# sheet2.net
KiCad netlist of a schematic drawn in Altium Designer
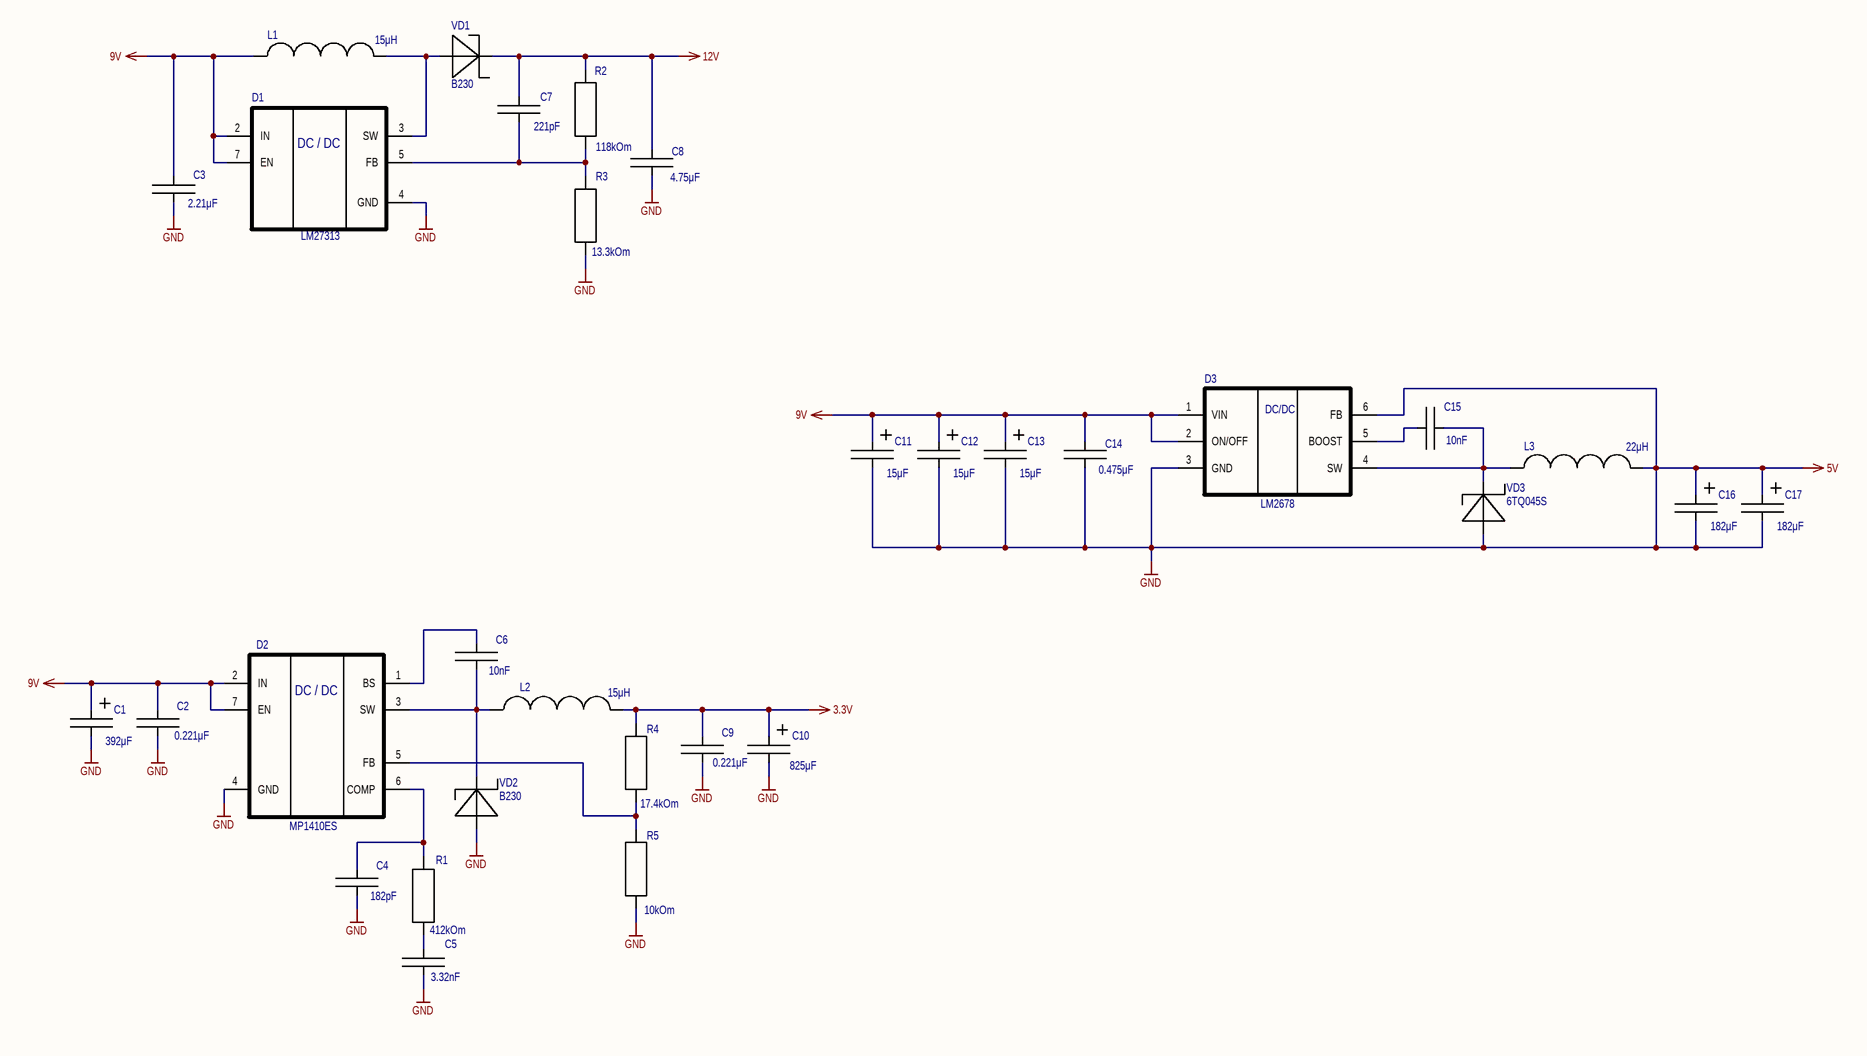
[diagram p0: sheet2.SchDoc]

(export (version "E")
  (design (tool "Eeschema 10.0.6"))
  (components
    (comp (ref "C1")
      (value "392μF")
      (fields (field (name "Comment") "392μFФ ±* * * *, *"))
      (libsource (lib "STO") (part "C+"))
    )
    (comp (ref "C2")
      (value "0.221μF")
      (fields (field (name "Comment") "0.221μFФ ±* * * *, *"))
      (libsource (lib "STO") (part "C"))
    )
    (comp (ref "C3")
      (value "2.21μF")
      (fields (field (name "Comment") "2.21μFФ ±* * * *, *"))
      (libsource (lib "STO") (part "C"))
    )
    (comp (ref "C4")
      (value "182pF")
      (fields (field (name "Comment") "182pFФ ±* * * *, *"))
      (libsource (lib "STO") (part "C"))
    )
    (comp (ref "C5")
      (value "3.32nF")
      (fields (field (name "Comment") "3.32nFФ ±* * * *, *"))
      (libsource (lib "STO") (part "C"))
    )
    (comp (ref "C6")
      (value "10nF")
      (fields (field (name "Comment") "10nFФ ±* * * *, *"))
      (libsource (lib "STO") (part "C"))
    )
    (comp (ref "C7")
      (value "221pF")
      (fields (field (name "Comment") "221pFФ ±* * * *, *"))
      (libsource (lib "STO") (part "C"))
    )
    (comp (ref "C8")
      (value "4.75μF")
      (fields (field (name "Comment") "4.75μFФ ±* * * *, *"))
      (libsource (lib "STO") (part "C"))
    )
    (comp (ref "C9")
      (value "0.221μF")
      (fields (field (name "Comment") "0.221μFФ ±* * * *, *"))
      (libsource (lib "STO") (part "C"))
    )
    (comp (ref "C10")
      (value "825μF")
      (fields (field (name "VOLTAGE") "6.3V") (field (name "Comment") "825μFФ ±* 6.3V * *, *"))
      (libsource (lib "STO") (part "C+"))
    )
    (comp (ref "C11")
      (value "15μF")
      (fields (field (name "Comment") "15μFФ ±* * * *, *"))
      (libsource (lib "STO") (part "C+"))
    )
    (comp (ref "C12")
      (value "15μF")
      (fields (field (name "Comment") "15μFФ ±* * * *, *"))
      (libsource (lib "STO") (part "C+"))
    )
    (comp (ref "C13")
      (value "15μF")
      (fields (field (name "Comment") "15μFФ ±* * * *, *"))
      (libsource (lib "STO") (part "C+"))
    )
    (comp (ref "C14")
      (value "0.475μF")
      (fields (field (name "Comment") "0.475μFФ ±* * * *, *"))
      (libsource (lib "STO") (part "C"))
    )
    (comp (ref "C15")
      (value "10nF")
      (fields (field (name "Comment") "10nFФ ±* * * *, *"))
      (libsource (lib "STO") (part "C"))
    )
    (comp (ref "C16")
      (value "182μF")
      (fields (field (name "Comment") "182μFФ ±* * * *, *"))
      (libsource (lib "STO") (part "C+"))
    )
    (comp (ref "C17")
      (value "182μF")
      (fields (field (name "Comment") "182μFФ ±* * * *, *"))
      (libsource (lib "STO") (part "C+"))
    )
    (comp (ref "D1") (value "LM27313") (libsource (lib "dop_elements") (part "LM27313")))
    (comp (ref "D2") (value "MP1410ES") (libsource (lib "dop_elements") (part "MP1410ES")))
    (comp (ref "D3") (value "LM2678") (libsource (lib "dop_elements") (part "LM2678")))
    (comp (ref "L1") (value "15μH") (libsource (lib "dop_elements") (part "L")))
    (comp (ref "L2") (value "15μH") (libsource (lib "dop_elements") (part "L")))
    (comp (ref "L3") (value "22μH") (libsource (lib "dop_elements") (part "L")))
    (comp (ref "R1")
      (value "412kOm")
      (fields (field (name "Comment") "412kOmОм ±* *, *"))
      (libsource (lib "STO") (part "R"))
    )
    (comp (ref "R2")
      (value "118kOm")
      (fields (field (name "Comment") "118kOmОм ±* *, *"))
      (libsource (lib "STO") (part "R"))
    )
    (comp (ref "R3")
      (value "13.3kOm")
      (fields (field (name "Comment") "13.3kOmОм ±* *, *"))
      (libsource (lib "STO") (part "R"))
    )
    (comp (ref "R4")
      (value "17.4kOm")
      (fields (field (name "Comment") "17.4kOmОм ±* *, *"))
      (libsource (lib "STO") (part "R"))
    )
    (comp (ref "R5")
      (value "10kOm")
      (fields (field (name "Comment") "10kOmОм ±* *, *"))
      (libsource (lib "STO") (part "R"))
    )
    (comp (ref "VD1") (value "B230") (libsource (lib "dop_elements") (part "diode_shottki")))
    (comp (ref "VD2") (value "B230") (libsource (lib "dop_elements") (part "diode_shottki")))
    (comp (ref "VD3") (value "6TQ045S") (libsource (lib "dop_elements") (part "diode_shottki")))
  )
  (nets
    (net (code "1") (name "3.3V") (class "Default")
      (node (ref "C10") (pin "1") (pinfunction "1_1") (pintype "passive"))
      (node (ref "C9") (pin "2") (pinfunction "2_2") (pintype "passive"))
      (node (ref "L2") (pin "9") (pinfunction "9_9") (pintype "passive"))
      (node (ref "R4") (pin "2") (pinfunction "2_2") (pintype "passive"))
    )
    (net (code "2") (name "5V") (class "Default")
      (node (ref "C1") (pin "2") (pinfunction "2_2") (pintype "passive"))
      (node (ref "C10") (pin "2") (pinfunction "2_2") (pintype "passive"))
      (node (ref "C11") (pin "2") (pinfunction "2_2") (pintype "passive"))
      (node (ref "C12") (pin "2") (pinfunction "2_2") (pintype "passive"))
      (node (ref "C13") (pin "2") (pinfunction "2_2") (pintype "passive"))
      (node (ref "C14") (pin "1") (pinfunction "1_1") (pintype "passive"))
      (node (ref "C16") (pin "1") (pinfunction "1_1") (pintype "passive"))
      (node (ref "C16") (pin "2") (pinfunction "2_2") (pintype "passive"))
      (node (ref "C17") (pin "1") (pinfunction "1_1") (pintype "passive"))
      (node (ref "C17") (pin "2") (pinfunction "2_2") (pintype "passive"))
      (node (ref "C2") (pin "1") (pinfunction "1_1") (pintype "passive"))
      (node (ref "C3") (pin "1") (pinfunction "1_1") (pintype "passive"))
      (node (ref "C4") (pin "1") (pinfunction "1_1") (pintype "passive"))
      (node (ref "C5") (pin "1") (pinfunction "1_1") (pintype "passive"))
      (node (ref "C8") (pin "1") (pinfunction "1_1") (pintype "passive"))
      (node (ref "C9") (pin "1") (pinfunction "1_1") (pintype "passive"))
      (node (ref "D1") (pin "4") (pinfunction "GND_4") (pintype "passive"))
      (node (ref "D2") (pin "4") (pinfunction "GND_4") (pintype "passive"))
      (node (ref "D3") (pin "3") (pinfunction "GND_3") (pintype "passive"))
      (node (ref "D3") (pin "6") (pinfunction "FB_6") (pintype "passive"))
      (node (ref "L3") (pin "9") (pinfunction "9_9") (pintype "passive"))
      (node (ref "R3") (pin "2") (pinfunction "2_2") (pintype "passive"))
      (node (ref "R5") (pin "1") (pinfunction "1_1") (pintype "passive"))
      (node (ref "VD2") (pin "10") (pinfunction "10_10") (pintype "passive"))
      (node (ref "VD3") (pin "10") (pinfunction "10_10") (pintype "passive"))
    )
    (net (code "3") (name "9V") (class "Default")
      (node (ref "C1") (pin "1") (pinfunction "1_1") (pintype "passive"))
      (node (ref "C11") (pin "1") (pinfunction "1_1") (pintype "passive"))
      (node (ref "C12") (pin "1") (pinfunction "1_1") (pintype "passive"))
      (node (ref "C13") (pin "1") (pinfunction "1_1") (pintype "passive"))
      (node (ref "C14") (pin "2") (pinfunction "2_2") (pintype "passive"))
      (node (ref "C2") (pin "2") (pinfunction "2_2") (pintype "passive"))
      (node (ref "C3") (pin "2") (pinfunction "2_2") (pintype "passive"))
      (node (ref "D1") (pin "2") (pinfunction "IN_2") (pintype "passive"))
      (node (ref "D1") (pin "7") (pinfunction "EN_7") (pintype "passive"))
      (node (ref "D2") (pin "2") (pinfunction "IN_2") (pintype "passive"))
      (node (ref "D2") (pin "7") (pinfunction "EN_7") (pintype "passive"))
      (node (ref "D3") (pin "1") (pinfunction "VIN_1") (pintype "passive"))
      (node (ref "D3") (pin "2") (pinfunction "ON/OFF_2") (pintype "passive"))
      (node (ref "L1") (pin "8") (pinfunction "8_8") (pintype "passive"))
    )
    (net (code "4") (name "12V") (class "Default")
      (node (ref "C7") (pin "2") (pinfunction "2_2") (pintype "passive"))
      (node (ref "C8") (pin "2") (pinfunction "2_2") (pintype "passive"))
      (node (ref "R2") (pin "1") (pinfunction "1_1") (pintype "passive"))
      (node (ref "VD1") (pin "11") (pinfunction "11_11") (pintype "passive"))
    )
    (net (code "5") (name "Net-(C5-Pad2)") (class "Default")
      (node (ref "C5") (pin "2") (pinfunction "2_2") (pintype "passive"))
      (node (ref "R1") (pin "1") (pinfunction "1_1") (pintype "passive"))
    )
    (net (code "6") (name "Net-(D1-FB)") (class "Default")
      (node (ref "C7") (pin "1") (pinfunction "1_1") (pintype "passive"))
      (node (ref "D1") (pin "5") (pinfunction "FB_5") (pintype "passive"))
      (node (ref "R2") (pin "2") (pinfunction "2_2") (pintype "passive"))
      (node (ref "R3") (pin "1") (pinfunction "1_1") (pintype "passive"))
    )
    (net (code "7") (name "Net-(D1-SW)") (class "Default")
      (node (ref "D1") (pin "3") (pinfunction "SW_3") (pintype "passive"))
      (node (ref "L1") (pin "9") (pinfunction "9_9") (pintype "passive"))
      (node (ref "VD1") (pin "10") (pinfunction "10_10") (pintype "passive"))
    )
    (net (code "8") (name "Net-(D2-BS)") (class "Default")
      (node (ref "C6") (pin "2") (pinfunction "2_2") (pintype "passive"))
      (node (ref "D2") (pin "1") (pinfunction "BS_1") (pintype "passive"))
    )
    (net (code "9") (name "Net-(D2-COMP)") (class "Default")
      (node (ref "C4") (pin "2") (pinfunction "2_2") (pintype "passive"))
      (node (ref "D2") (pin "6") (pinfunction "COMP_6") (pintype "passive"))
      (node (ref "R1") (pin "2") (pinfunction "2_2") (pintype "passive"))
    )
    (net (code "10") (name "Net-(D2-FB)") (class "Default")
      (node (ref "D2") (pin "5") (pinfunction "FB_5") (pintype "passive"))
      (node (ref "R4") (pin "1") (pinfunction "1_1") (pintype "passive"))
      (node (ref "R5") (pin "2") (pinfunction "2_2") (pintype "passive"))
    )
    (net (code "11") (name "Net-(D2-SW)") (class "Default")
      (node (ref "C6") (pin "1") (pinfunction "1_1") (pintype "passive"))
      (node (ref "D2") (pin "3") (pinfunction "SW_3") (pintype "passive"))
      (node (ref "L2") (pin "8") (pinfunction "8_8") (pintype "passive"))
      (node (ref "VD2") (pin "11") (pinfunction "11_11") (pintype "passive"))
    )
    (net (code "12") (name "Net-(D3-BOOST)") (class "Default")
      (node (ref "C15") (pin "2") (pinfunction "2_2") (pintype "passive"))
      (node (ref "D3") (pin "5") (pinfunction "BOOST_5") (pintype "passive"))
    )
    (net (code "13") (name "Net-(D3-SW)") (class "Default")
      (node (ref "C15") (pin "1") (pinfunction "1_1") (pintype "passive"))
      (node (ref "D3") (pin "4") (pinfunction "SW_4") (pintype "passive"))
      (node (ref "L3") (pin "8") (pinfunction "8_8") (pintype "passive"))
      (node (ref "VD3") (pin "11") (pinfunction "11_11") (pintype "passive"))
    )
  )
)
